# 00_EEG_AFE.net
KiCad netlist of a schematic drawn in Altium Designer
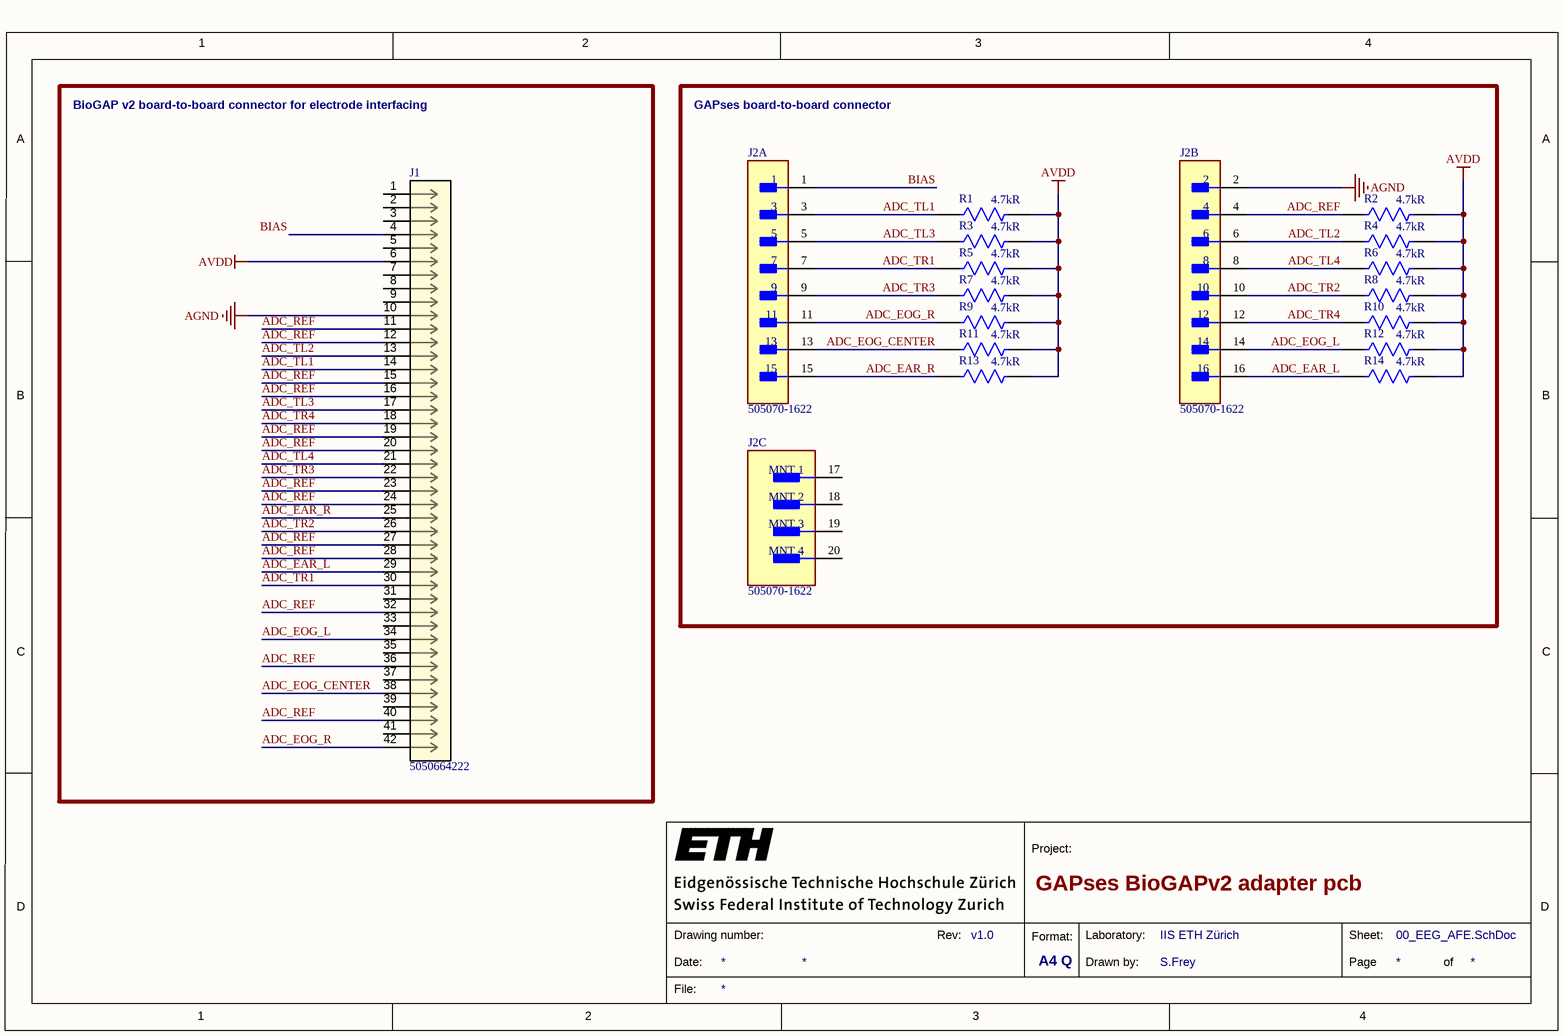
[diagram p0: 00_EEG_AFE.SchDoc]

(export (version "E")
  (design (tool "Eeschema 10.0.6"))
  (components
    (comp (ref "J1")
      (value "5050664222")
      (footprint "CONN_5050664222_MOL")
      (description "No Description Available")
      (libsource (lib "EEG_SchLib") (part "5050664222"))
    )
    (comp (ref "J2")
      (value "505070-1622")
      (footprint "FP-505070-1622-MFG")
      (description "CONN PLUG 16POS SMD GOLD")
      (libsource (lib "Altium Content Vault") (part "71c7bd868a703cb05f67e14b15c5ca9"))
    )
    (comp (ref "R1")
      (value "RR0510P-472-D")
      (footprint "FP-RR0510-IPC_C")
      (description "4.7kΩ ±0.5% 0.0625W 1/16W Chip Resistor 0402 (1005 Metric) Thin Film")
      (fields (field (name "TOLERANCE") "0.5%") (field (name "RESISTANCE") "4.7kR"))
      (libsource (lib "Altium Content Vault") (part "1029c3af85768c4190bb7ad29bc67b5"))
    )
    (comp (ref "R2")
      (value "RR0510P-472-D")
      (footprint "FP-RR0510-IPC_C")
      (description "4.7kΩ ±0.5% 0.0625W 1/16W Chip Resistor 0402 (1005 Metric) Thin Film")
      (fields (field (name "TOLERANCE") "0.5%") (field (name "RESISTANCE") "4.7kR"))
      (libsource (lib "Altium Content Vault") (part "1029c3af85768c4190bb7ad29bc67b5"))
    )
    (comp (ref "R3")
      (value "RR0510P-472-D")
      (footprint "FP-RR0510-IPC_C")
      (description "4.7kΩ ±0.5% 0.0625W 1/16W Chip Resistor 0402 (1005 Metric) Thin Film")
      (fields (field (name "TOLERANCE") "0.5%") (field (name "RESISTANCE") "4.7kR"))
      (libsource (lib "Altium Content Vault") (part "1029c3af85768c4190bb7ad29bc67b5"))
    )
    (comp (ref "R4")
      (value "RR0510P-472-D")
      (footprint "FP-RR0510-IPC_C")
      (description "4.7kΩ ±0.5% 0.0625W 1/16W Chip Resistor 0402 (1005 Metric) Thin Film")
      (fields (field (name "TOLERANCE") "0.5%") (field (name "RESISTANCE") "4.7kR"))
      (libsource (lib "Altium Content Vault") (part "1029c3af85768c4190bb7ad29bc67b5"))
    )
    (comp (ref "R5")
      (value "RR0510P-472-D")
      (footprint "FP-RR0510-IPC_C")
      (description "4.7kΩ ±0.5% 0.0625W 1/16W Chip Resistor 0402 (1005 Metric) Thin Film")
      (fields (field (name "TOLERANCE") "0.5%") (field (name "RESISTANCE") "4.7kR"))
      (libsource (lib "Altium Content Vault") (part "1029c3af85768c4190bb7ad29bc67b5"))
    )
    (comp (ref "R6")
      (value "RR0510P-472-D")
      (footprint "FP-RR0510-IPC_C")
      (description "4.7kΩ ±0.5% 0.0625W 1/16W Chip Resistor 0402 (1005 Metric) Thin Film")
      (fields (field (name "TOLERANCE") "0.5%") (field (name "RESISTANCE") "4.7kR"))
      (libsource (lib "Altium Content Vault") (part "1029c3af85768c4190bb7ad29bc67b5"))
    )
    (comp (ref "R7")
      (value "RR0510P-472-D")
      (footprint "FP-RR0510-IPC_C")
      (description "4.7kΩ ±0.5% 0.0625W 1/16W Chip Resistor 0402 (1005 Metric) Thin Film")
      (fields (field (name "TOLERANCE") "0.5%") (field (name "RESISTANCE") "4.7kR"))
      (libsource (lib "Altium Content Vault") (part "1029c3af85768c4190bb7ad29bc67b5"))
    )
    (comp (ref "R8")
      (value "RR0510P-472-D")
      (footprint "FP-RR0510-IPC_C")
      (description "4.7kΩ ±0.5% 0.0625W 1/16W Chip Resistor 0402 (1005 Metric) Thin Film")
      (fields (field (name "TOLERANCE") "0.5%") (field (name "RESISTANCE") "4.7kR"))
      (libsource (lib "Altium Content Vault") (part "1029c3af85768c4190bb7ad29bc67b5"))
    )
    (comp (ref "R9")
      (value "RR0510P-472-D")
      (footprint "FP-RR0510-IPC_C")
      (description "4.7kΩ ±0.5% 0.0625W 1/16W Chip Resistor 0402 (1005 Metric) Thin Film")
      (fields (field (name "TOLERANCE") "0.5%") (field (name "RESISTANCE") "4.7kR"))
      (libsource (lib "Altium Content Vault") (part "1029c3af85768c4190bb7ad29bc67b5"))
    )
    (comp (ref "R10")
      (value "RR0510P-472-D")
      (footprint "FP-RR0510-IPC_C")
      (description "4.7kΩ ±0.5% 0.0625W 1/16W Chip Resistor 0402 (1005 Metric) Thin Film")
      (fields (field (name "TOLERANCE") "0.5%") (field (name "RESISTANCE") "4.7kR"))
      (libsource (lib "Altium Content Vault") (part "1029c3af85768c4190bb7ad29bc67b5"))
    )
    (comp (ref "R11")
      (value "RR0510P-472-D")
      (footprint "FP-RR0510-IPC_C")
      (description "4.7kΩ ±0.5% 0.0625W 1/16W Chip Resistor 0402 (1005 Metric) Thin Film")
      (fields (field (name "TOLERANCE") "0.5%") (field (name "RESISTANCE") "4.7kR"))
      (libsource (lib "Altium Content Vault") (part "1029c3af85768c4190bb7ad29bc67b5"))
    )
    (comp (ref "R12")
      (value "RR0510P-472-D")
      (footprint "FP-RR0510-IPC_C")
      (description "4.7kΩ ±0.5% 0.0625W 1/16W Chip Resistor 0402 (1005 Metric) Thin Film")
      (fields (field (name "TOLERANCE") "0.5%") (field (name "RESISTANCE") "4.7kR"))
      (libsource (lib "Altium Content Vault") (part "1029c3af85768c4190bb7ad29bc67b5"))
    )
    (comp (ref "R13")
      (value "RR0510P-472-D")
      (footprint "FP-RR0510-IPC_C")
      (description "4.7kΩ ±0.5% 0.0625W 1/16W Chip Resistor 0402 (1005 Metric) Thin Film")
      (fields (field (name "TOLERANCE") "0.5%") (field (name "RESISTANCE") "4.7kR"))
      (libsource (lib "Altium Content Vault") (part "1029c3af85768c4190bb7ad29bc67b5"))
    )
    (comp (ref "R14")
      (value "RR0510P-472-D")
      (footprint "FP-RR0510-IPC_C")
      (description "4.7kΩ ±0.5% 0.0625W 1/16W Chip Resistor 0402 (1005 Metric) Thin Film")
      (fields (field (name "TOLERANCE") "0.5%") (field (name "RESISTANCE") "4.7kR"))
      (libsource (lib "Altium Content Vault") (part "1029c3af85768c4190bb7ad29bc67b5"))
    )
  )
  (nets
    (net (code "1") (name "/ADC_EAR_L") (class "Default")
      (node (ref "J1") (pin "29") (pinfunction "29_29") (pintype "passive"))
      (node (ref "J2") (pin "16") (pinfunction "16_16") (pintype "passive"))
      (node (ref "R14") (pin "1") (pinfunction "1_1") (pintype "passive"))
    )
    (net (code "2") (name "/ADC_EAR_R") (class "Default")
      (node (ref "J1") (pin "25") (pinfunction "25_25") (pintype "passive"))
      (node (ref "J2") (pin "15") (pinfunction "15_15") (pintype "passive"))
      (node (ref "R13") (pin "1") (pinfunction "1_1") (pintype "passive"))
    )
    (net (code "3") (name "/ADC_EOG_CENTER") (class "Default")
      (node (ref "J1") (pin "38") (pinfunction "38_38") (pintype "passive"))
      (node (ref "J2") (pin "13") (pinfunction "13_13") (pintype "passive"))
      (node (ref "R11") (pin "1") (pinfunction "1_1") (pintype "passive"))
    )
    (net (code "4") (name "/ADC_EOG_L") (class "Default")
      (node (ref "J1") (pin "34") (pinfunction "34_34") (pintype "passive"))
      (node (ref "J2") (pin "14") (pinfunction "14_14") (pintype "passive"))
      (node (ref "R12") (pin "1") (pinfunction "1_1") (pintype "passive"))
    )
    (net (code "5") (name "/ADC_EOG_R") (class "Default")
      (node (ref "J1") (pin "42") (pinfunction "42_42") (pintype "passive"))
      (node (ref "J2") (pin "11") (pinfunction "11_11") (pintype "passive"))
      (node (ref "R9") (pin "1") (pinfunction "1_1") (pintype "passive"))
    )
    (net (code "6") (name "/ADC_REF") (class "Default")
      (node (ref "J1") (pin "11") (pinfunction "11_11") (pintype "passive"))
      (node (ref "J1") (pin "12") (pinfunction "12_12") (pintype "passive"))
      (node (ref "J1") (pin "15") (pinfunction "15_15") (pintype "passive"))
      (node (ref "J1") (pin "16") (pinfunction "16_16") (pintype "passive"))
      (node (ref "J1") (pin "19") (pinfunction "19_19") (pintype "passive"))
      (node (ref "J1") (pin "20") (pinfunction "20_20") (pintype "passive"))
      (node (ref "J1") (pin "23") (pinfunction "23_23") (pintype "passive"))
      (node (ref "J1") (pin "24") (pinfunction "24_24") (pintype "passive"))
      (node (ref "J1") (pin "27") (pinfunction "27_27") (pintype "passive"))
      (node (ref "J1") (pin "28") (pinfunction "28_28") (pintype "passive"))
      (node (ref "J1") (pin "32") (pinfunction "32_32") (pintype "passive"))
      (node (ref "J1") (pin "36") (pinfunction "36_36") (pintype "passive"))
      (node (ref "J1") (pin "40") (pinfunction "40_40") (pintype "passive"))
      (node (ref "J2") (pin "4") (pinfunction "4_4") (pintype "passive"))
      (node (ref "R2") (pin "1") (pinfunction "1_1") (pintype "passive"))
    )
    (net (code "7") (name "/ADC_TL1") (class "Default")
      (node (ref "J1") (pin "14") (pinfunction "14_14") (pintype "passive"))
      (node (ref "J2") (pin "3") (pinfunction "3_3") (pintype "passive"))
      (node (ref "R1") (pin "1") (pinfunction "1_1") (pintype "passive"))
    )
    (net (code "8") (name "/ADC_TL2") (class "Default")
      (node (ref "J1") (pin "13") (pinfunction "13_13") (pintype "passive"))
      (node (ref "J2") (pin "6") (pinfunction "6_6") (pintype "passive"))
      (node (ref "R4") (pin "1") (pinfunction "1_1") (pintype "passive"))
    )
    (net (code "9") (name "/ADC_TL3") (class "Default")
      (node (ref "J1") (pin "17") (pinfunction "17_17") (pintype "passive"))
      (node (ref "J2") (pin "5") (pinfunction "5_5") (pintype "passive"))
      (node (ref "R3") (pin "1") (pinfunction "1_1") (pintype "passive"))
    )
    (net (code "10") (name "/ADC_TL4") (class "Default")
      (node (ref "J1") (pin "21") (pinfunction "21_21") (pintype "passive"))
      (node (ref "J2") (pin "8") (pinfunction "8_8") (pintype "passive"))
      (node (ref "R6") (pin "1") (pinfunction "1_1") (pintype "passive"))
    )
    (net (code "11") (name "/ADC_TR1") (class "Default")
      (node (ref "J1") (pin "30") (pinfunction "30_30") (pintype "passive"))
      (node (ref "J2") (pin "7") (pinfunction "7_7") (pintype "passive"))
      (node (ref "R5") (pin "1") (pinfunction "1_1") (pintype "passive"))
    )
    (net (code "12") (name "/ADC_TR2") (class "Default")
      (node (ref "J1") (pin "26") (pinfunction "26_26") (pintype "passive"))
      (node (ref "J2") (pin "10") (pinfunction "10_10") (pintype "passive"))
      (node (ref "R8") (pin "1") (pinfunction "1_1") (pintype "passive"))
    )
    (net (code "13") (name "/ADC_TR3") (class "Default")
      (node (ref "J1") (pin "22") (pinfunction "22_22") (pintype "passive"))
      (node (ref "J2") (pin "9") (pinfunction "9_9") (pintype "passive"))
      (node (ref "R7") (pin "1") (pinfunction "1_1") (pintype "passive"))
    )
    (net (code "14") (name "/ADC_TR4") (class "Default")
      (node (ref "J1") (pin "18") (pinfunction "18_18") (pintype "passive"))
      (node (ref "J2") (pin "12") (pinfunction "12_12") (pintype "passive"))
      (node (ref "R10") (pin "1") (pinfunction "1_1") (pintype "passive"))
    )
    (net (code "15") (name "/BIAS") (class "Default")
      (node (ref "J1") (pin "4") (pinfunction "4_4") (pintype "passive"))
      (node (ref "J2") (pin "1") (pinfunction "1_1") (pintype "passive"))
    )
    (net (code "16") (name "AGND") (class "Default")
      (node (ref "J1") (pin "10") (pinfunction "10_10") (pintype "passive"))
      (node (ref "J2") (pin "2") (pinfunction "2_2") (pintype "passive"))
    )
    (net (code "17") (name "AVDD") (class "Default")
      (node (ref "J1") (pin "6") (pinfunction "6_6") (pintype "passive"))
      (node (ref "R1") (pin "2") (pinfunction "2_2") (pintype "passive"))
      (node (ref "R10") (pin "2") (pinfunction "2_2") (pintype "passive"))
      (node (ref "R11") (pin "2") (pinfunction "2_2") (pintype "passive"))
      (node (ref "R12") (pin "2") (pinfunction "2_2") (pintype "passive"))
      (node (ref "R13") (pin "2") (pinfunction "2_2") (pintype "passive"))
      (node (ref "R14") (pin "2") (pinfunction "2_2") (pintype "passive"))
      (node (ref "R2") (pin "2") (pinfunction "2_2") (pintype "passive"))
      (node (ref "R3") (pin "2") (pinfunction "2_2") (pintype "passive"))
      (node (ref "R4") (pin "2") (pinfunction "2_2") (pintype "passive"))
      (node (ref "R5") (pin "2") (pinfunction "2_2") (pintype "passive"))
      (node (ref "R6") (pin "2") (pinfunction "2_2") (pintype "passive"))
      (node (ref "R7") (pin "2") (pinfunction "2_2") (pintype "passive"))
      (node (ref "R8") (pin "2") (pinfunction "2_2") (pintype "passive"))
      (node (ref "R9") (pin "2") (pinfunction "2_2") (pintype "passive"))
    )
    (net (code "18") (name "unconnected-(J1-Pad1)") (class "Default")
      (node (ref "J1") (pin "1") (pinfunction "1_1") (pintype "passive"))
    )
    (net (code "19") (name "unconnected-(J1-Pad2)") (class "Default")
      (node (ref "J1") (pin "2") (pinfunction "2_2") (pintype "passive"))
    )
    (net (code "20") (name "unconnected-(J1-Pad3)") (class "Default")
      (node (ref "J1") (pin "3") (pinfunction "3_3") (pintype "passive"))
    )
    (net (code "21") (name "unconnected-(J1-Pad5)") (class "Default")
      (node (ref "J1") (pin "5") (pinfunction "5_5") (pintype "passive"))
    )
    (net (code "22") (name "unconnected-(J1-Pad7)") (class "Default")
      (node (ref "J1") (pin "7") (pinfunction "7_7") (pintype "passive"))
    )
    (net (code "23") (name "unconnected-(J1-Pad8)") (class "Default")
      (node (ref "J1") (pin "8") (pinfunction "8_8") (pintype "passive"))
    )
    (net (code "24") (name "unconnected-(J1-Pad9)") (class "Default")
      (node (ref "J1") (pin "9") (pinfunction "9_9") (pintype "passive"))
    )
    (net (code "25") (name "unconnected-(J1-Pad31)") (class "Default")
      (node (ref "J1") (pin "31") (pinfunction "31_31") (pintype "passive"))
    )
    (net (code "26") (name "unconnected-(J1-Pad33)") (class "Default")
      (node (ref "J1") (pin "33") (pinfunction "33_33") (pintype "passive"))
    )
    (net (code "27") (name "unconnected-(J1-Pad35)") (class "Default")
      (node (ref "J1") (pin "35") (pinfunction "35_35") (pintype "passive"))
    )
    (net (code "28") (name "unconnected-(J1-Pad37)") (class "Default")
      (node (ref "J1") (pin "37") (pinfunction "37_37") (pintype "passive"))
    )
    (net (code "29") (name "unconnected-(J1-Pad39)") (class "Default")
      (node (ref "J1") (pin "39") (pinfunction "39_39") (pintype "passive"))
    )
    (net (code "30") (name "unconnected-(J1-Pad41)") (class "Default")
      (node (ref "J1") (pin "41") (pinfunction "41_41") (pintype "passive"))
    )
    (net (code "31") (name "unconnected-(J2C-MNT_1-Pad17)") (class "Default")
      (node (ref "J2") (pin "17") (pinfunction "MNT_1_17") (pintype "passive"))
    )
    (net (code "32") (name "unconnected-(J2C-MNT_2-Pad18)") (class "Default")
      (node (ref "J2") (pin "18") (pinfunction "MNT_2_18") (pintype "passive"))
    )
    (net (code "33") (name "unconnected-(J2C-MNT_3-Pad19)") (class "Default")
      (node (ref "J2") (pin "19") (pinfunction "MNT_3_19") (pintype "passive"))
    )
    (net (code "34") (name "unconnected-(J2C-MNT_4-Pad20)") (class "Default")
      (node (ref "J2") (pin "20") (pinfunction "MNT_4_20") (pintype "passive"))
    )
  )
)
